# 1.net
KiCad netlist of a schematic drawn in Altium Designer
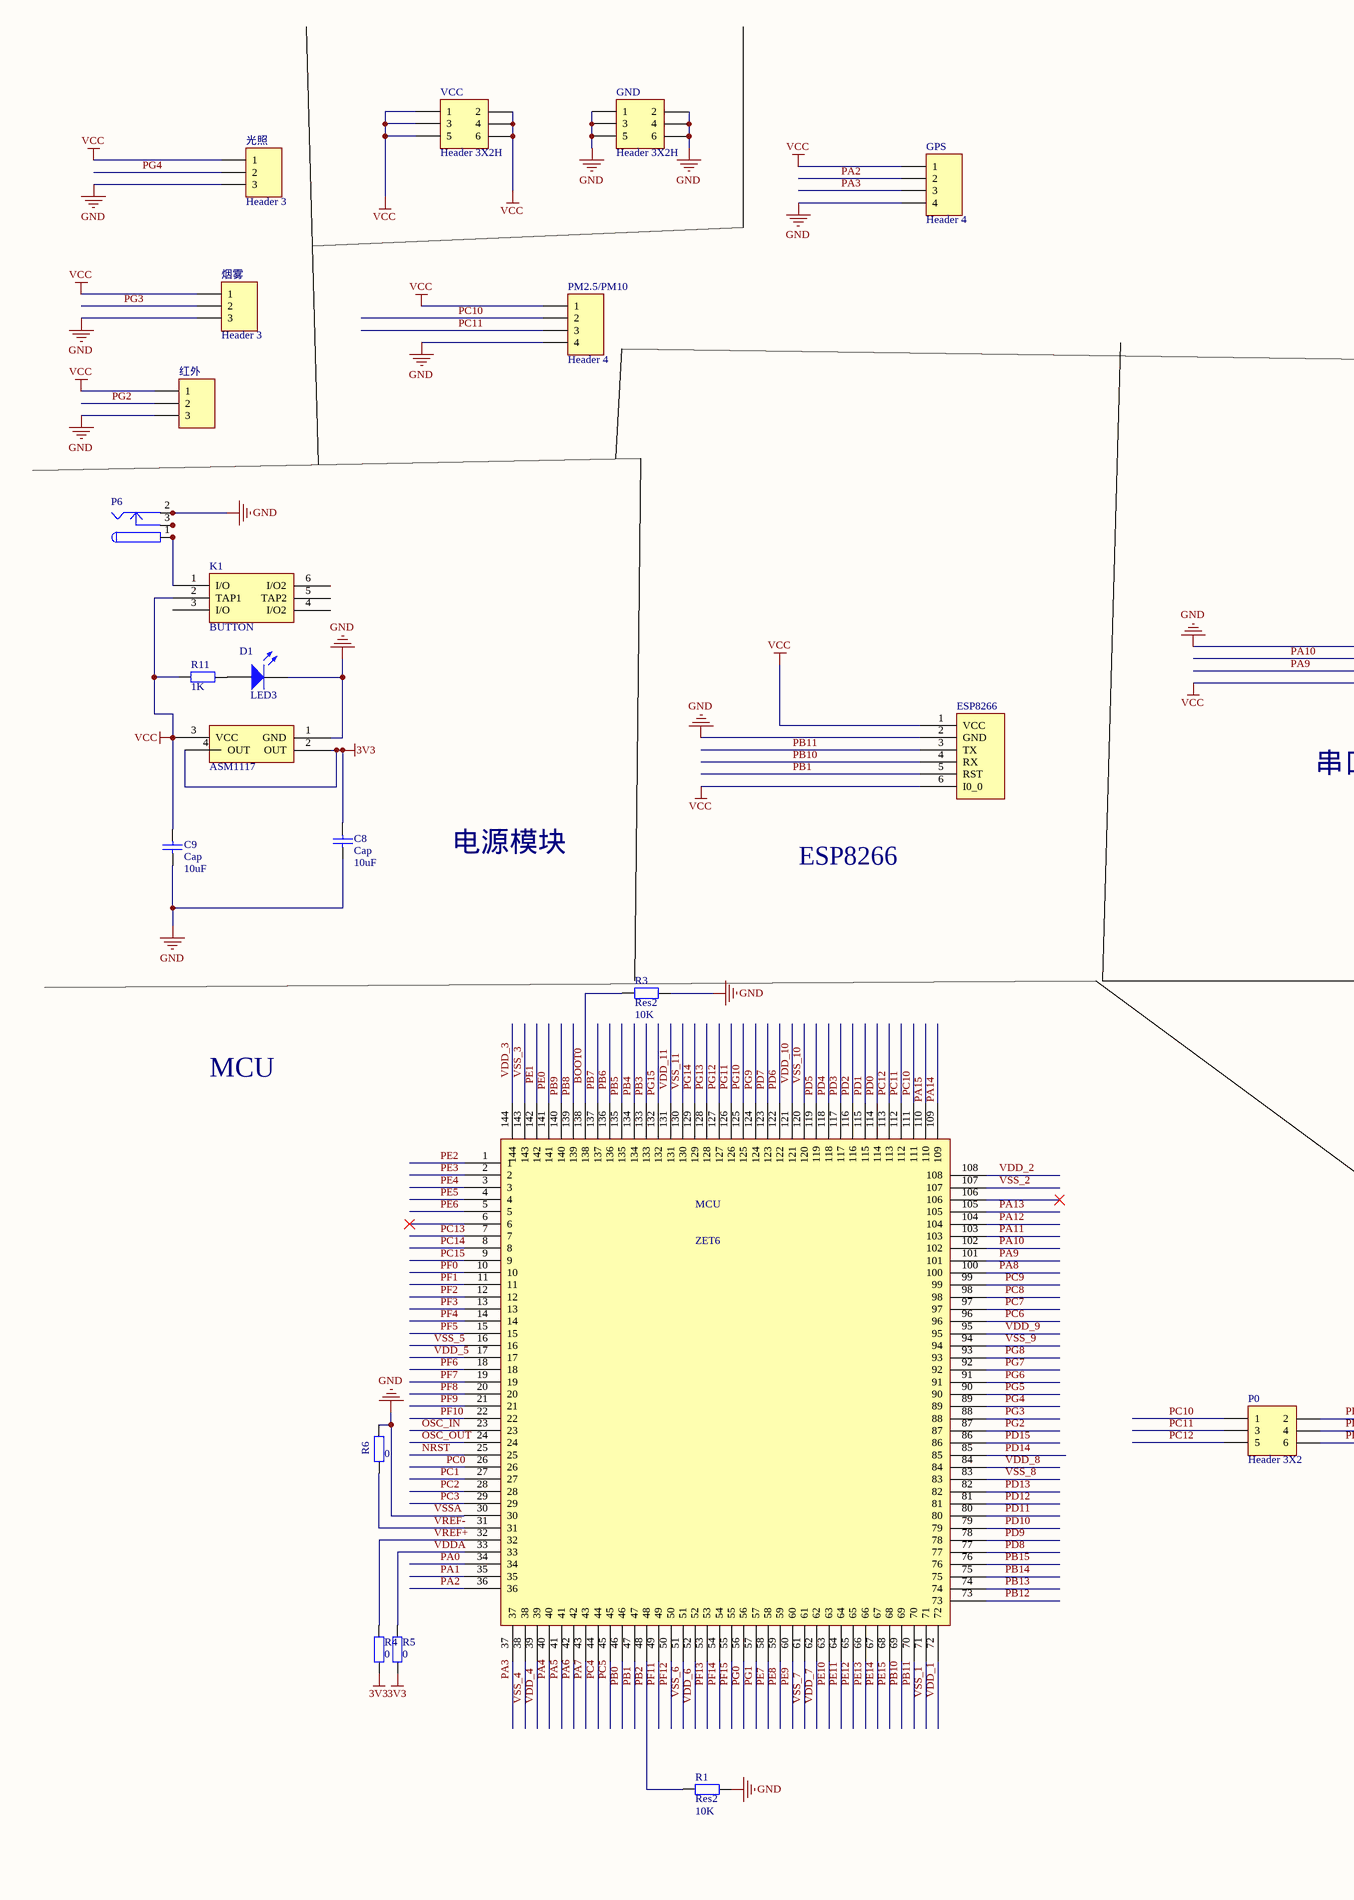
[diagram p0: 1.SchDoc, left]
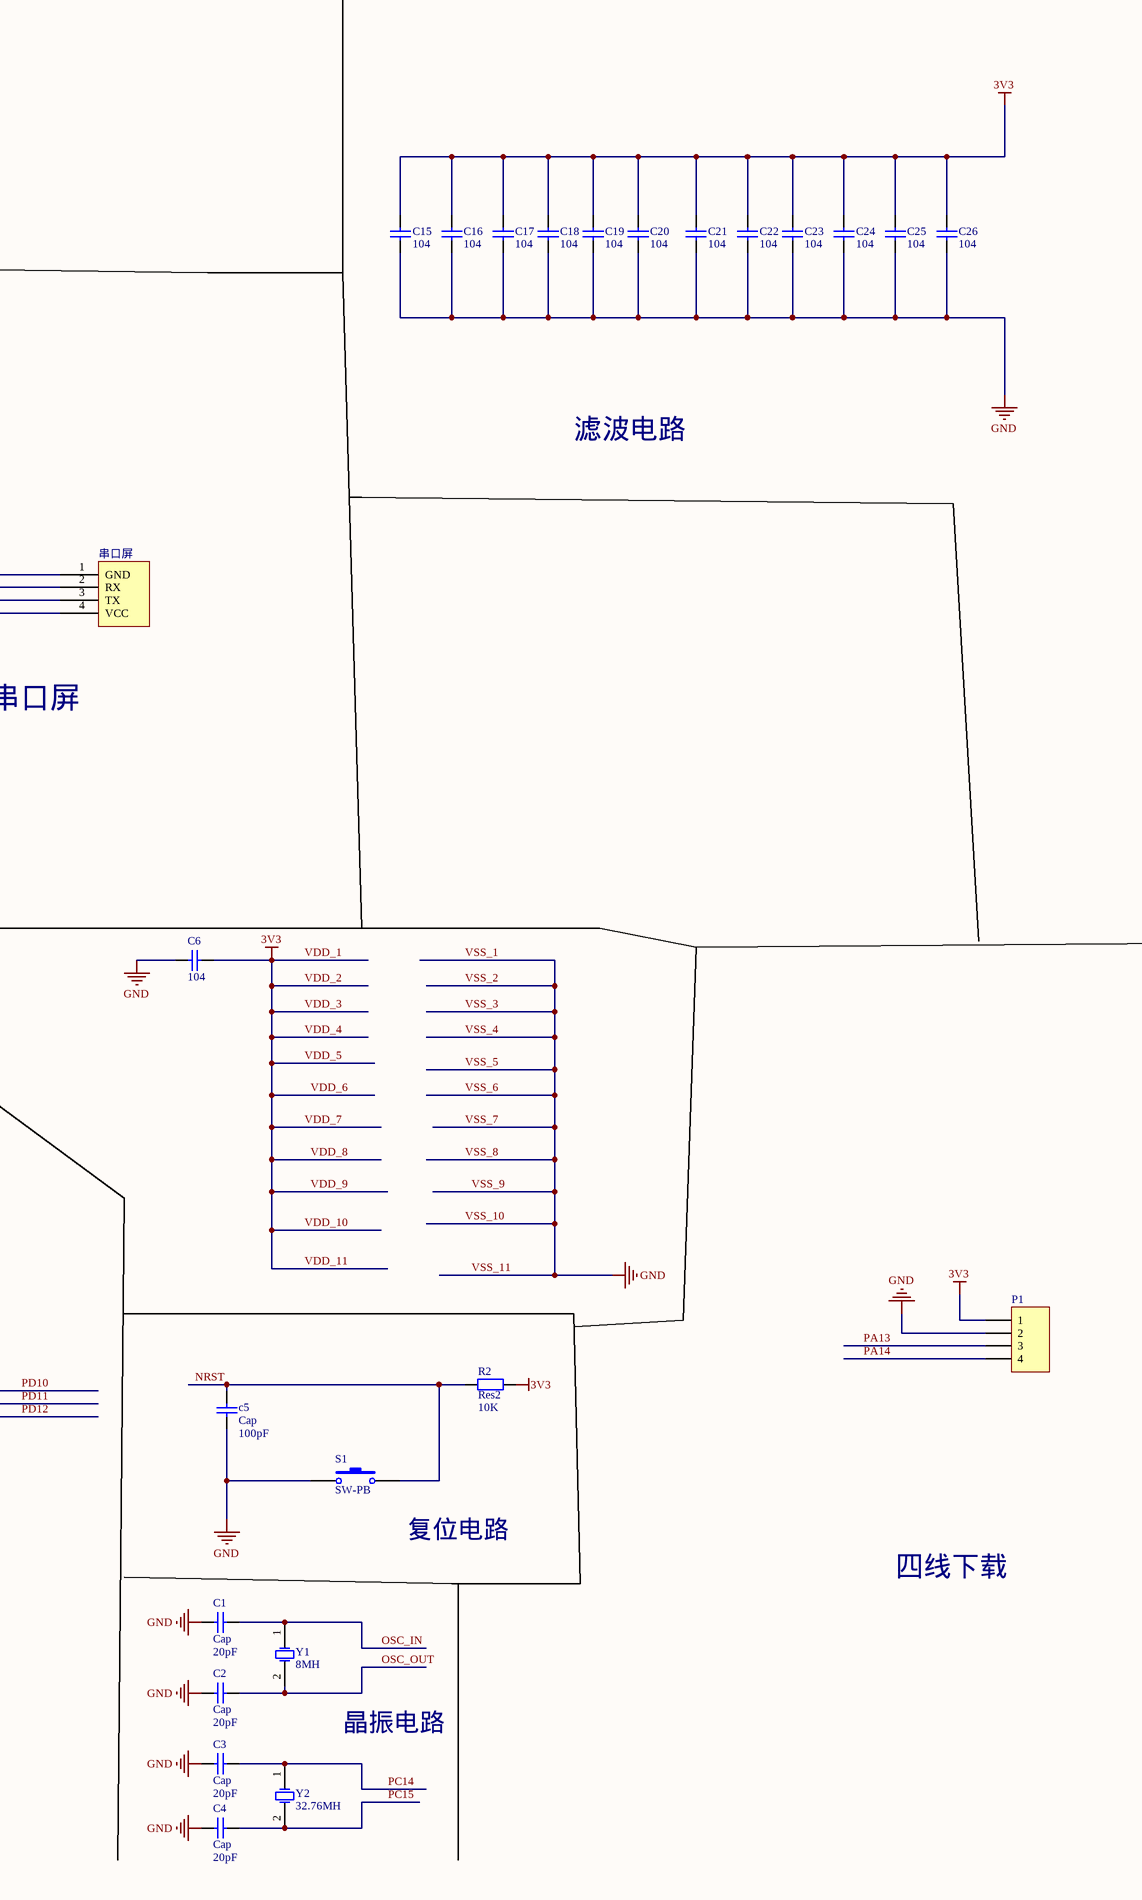
[diagram p1: 1.SchDoc, right]

(export (version "E")
  (design (tool "Eeschema 10.0.6"))
  (components
    (comp (ref "*") (value "ASM1117") (footprint "SOT-223") (libsource (lib "Schlib1") (part "ASM1117")))
    (comp (ref "C1")
      (value "Cap")
      (footprint "C0805")
      (description "Capacitor")
      (fields (field (name "ALTIUM_VALUE") "20pF") (field (name "PUBLISHER") "Altium Limited"))
      (libsource (lib "Miscellaneous Devices") (part "Cap"))
    )
    (comp (ref "C2")
      (value "Cap")
      (footprint "C0805")
      (description "Capacitor")
      (fields (field (name "ALTIUM_VALUE") "20pF") (field (name "PUBLISHER") "Altium Limited"))
      (libsource (lib "Miscellaneous Devices") (part "Cap"))
    )
    (comp (ref "C3")
      (value "Cap")
      (footprint "C0805")
      (description "Capacitor")
      (fields (field (name "ALTIUM_VALUE") "20pF") (field (name "PUBLISHER") "Altium Limited"))
      (libsource (lib "Miscellaneous Devices") (part "Cap"))
    )
    (comp (ref "C4")
      (value "Cap")
      (footprint "C0805")
      (description "Capacitor")
      (fields (field (name "ALTIUM_VALUE") "20pF") (field (name "PUBLISHER") "Altium Limited"))
      (libsource (lib "Miscellaneous Devices") (part "Cap"))
    )
    (comp (ref "c5")
      (value "Cap")
      (footprint "C0805")
      (description "Capacitor")
      (fields (field (name "ALTIUM_VALUE") "100pF") (field (name "PUBLISHER") "Altium Limited"))
      (libsource (lib "Miscellaneous Devices") (part "Cap"))
    )
    (comp (ref "C6")
      (value "104")
      (footprint "C0805")
      (description "Capacitor (Semiconductor SIM Model)")
      (fields (field (name "Comment") "Cap Semi") (field (name "PUBLISHER") "Altium Limited"))
      (libsource (lib "Miscellaneous Devices") (part "Cap Semi"))
    )
    (comp (ref "C8")
      (value "Cap")
      (footprint "C0805")
      (description "Capacitor")
      (fields (field (name "ALTIUM_VALUE") "10uF") (field (name "PUBLISHER") "Altium Limited"))
      (libsource (lib "Miscellaneous Devices") (part "Cap"))
    )
    (comp (ref "C9")
      (value "Cap")
      (footprint "C0805")
      (description "Capacitor")
      (fields (field (name "ALTIUM_VALUE") "10uF") (field (name "PUBLISHER") "Altium Limited"))
      (libsource (lib "Miscellaneous Devices") (part "Cap"))
    )
    (comp (ref "C15")
      (value "104")
      (footprint "C0805")
      (description "Capacitor")
      (fields (field (name "Comment") "Cap") (field (name "PUBLISHER") "Altium Limited"))
      (libsource (lib "Miscellaneous Devices") (part "Cap"))
    )
    (comp (ref "C16")
      (value "104")
      (footprint "C0805")
      (description "Capacitor")
      (fields (field (name "Comment") "Cap") (field (name "PUBLISHER") "Altium Limited"))
      (libsource (lib "Miscellaneous Devices") (part "Cap"))
    )
    (comp (ref "C17")
      (value "104")
      (footprint "C0805")
      (description "Capacitor")
      (fields (field (name "Comment") "Cap") (field (name "PUBLISHER") "Altium Limited"))
      (libsource (lib "Miscellaneous Devices") (part "Cap"))
    )
    (comp (ref "C18")
      (value "104")
      (footprint "C0805")
      (description "Capacitor")
      (fields (field (name "Comment") "Cap") (field (name "PUBLISHER") "Altium Limited"))
      (libsource (lib "Miscellaneous Devices") (part "Cap"))
    )
    (comp (ref "C19")
      (value "104")
      (footprint "C0805")
      (description "Capacitor")
      (fields (field (name "Comment") "Cap") (field (name "PUBLISHER") "Altium Limited"))
      (libsource (lib "Miscellaneous Devices") (part "Cap"))
    )
    (comp (ref "C20")
      (value "104")
      (footprint "C0805")
      (description "Capacitor")
      (fields (field (name "Comment") "Cap") (field (name "PUBLISHER") "Altium Limited"))
      (libsource (lib "Miscellaneous Devices") (part "Cap"))
    )
    (comp (ref "C21")
      (value "104")
      (footprint "C0805")
      (description "Capacitor")
      (fields (field (name "Comment") "Cap") (field (name "PUBLISHER") "Altium Limited"))
      (libsource (lib "Miscellaneous Devices") (part "Cap"))
    )
    (comp (ref "C22")
      (value "104")
      (footprint "C0805")
      (description "Capacitor")
      (fields (field (name "Comment") "Cap") (field (name "PUBLISHER") "Altium Limited"))
      (libsource (lib "Miscellaneous Devices") (part "Cap"))
    )
    (comp (ref "C23")
      (value "104")
      (footprint "C0805")
      (description "Capacitor")
      (fields (field (name "Comment") "Cap") (field (name "PUBLISHER") "Altium Limited"))
      (libsource (lib "Miscellaneous Devices") (part "Cap"))
    )
    (comp (ref "C24")
      (value "104")
      (footprint "C0805")
      (description "Capacitor")
      (fields (field (name "Comment") "Cap") (field (name "PUBLISHER") "Altium Limited"))
      (libsource (lib "Miscellaneous Devices") (part "Cap"))
    )
    (comp (ref "C25")
      (value "104")
      (footprint "C0805")
      (description "Capacitor")
      (fields (field (name "Comment") "Cap") (field (name "PUBLISHER") "Altium Limited"))
      (libsource (lib "Miscellaneous Devices") (part "Cap"))
    )
    (comp (ref "C26")
      (value "104")
      (footprint "C0805")
      (description "Capacitor")
      (fields (field (name "Comment") "Cap") (field (name "PUBLISHER") "Altium Limited"))
      (libsource (lib "Miscellaneous Devices") (part "Cap"))
    )
    (comp (ref "D1")
      (value "LED3")
      (footprint "RB.10")
      (description "Typical BLUE SiC LED")
      (fields (field (name "PUBLISHER") "Altium Limited"))
      (libsource (lib "Miscellaneous Devices") (part "LED3"))
    )
    (comp (ref "ESP8266") (value "A10") (footprint "HDR1X6") (libsource (lib "") (part "Component_1_1")))
    (comp (ref "GND")
      (value "Header 3X2H")
      (footprint "HDR2X3_CEN")
      (description "Header, 3-Pin, Dual row, Right Angle")
      (fields (field (name "PUBLISHER") "Altium Limited"))
      (libsource (lib "Miscellaneous Connectors") (part "Header 3X2H"))
    )
    (comp (ref "GPS")
      (value "Header 4")
      (footprint "HDR1X4")
      (description "Header, 4-Pin")
      (fields (field (name "PUBLISHER") "Altium Limited"))
      (libsource (lib "Miscellaneous Connectors") (part "Header 4"))
    )
    (comp (ref "K1") (value "BUTTON") (footprint "BTN8.5*8.5") (libsource (lib "Schlib1") (part "BUTTON")))
    (comp (ref "P0")
      (value "Header 3X2")
      (footprint "HDR2X3")
      (description "Header, 3-Pin, Dual row")
      (fields (field (name "PUBLISHER") "Altium Limited"))
      (libsource (lib "Miscellaneous Connectors") (part "Header 3X2"))
    )
    (comp (ref "P1")
      (value "Header 4")
      (footprint "HDR1X4")
      (description "Header, 4-Pin")
      (fields (field (name "PUBLISHER") "Altium Limited"))
      (libsource (lib "Miscellaneous Connectors") (part "Header 4"))
    )
    (comp (ref "P6")
      (value "PWR2.5")
      (footprint "DCIN")
      (description "Low Voltage Power Supply Connector")
      (fields (field (name "PUBLISHER") "Altium Limited"))
      (libsource (lib "Miscellaneous Connectors") (part "PWR2.5"))
    )
    (comp (ref "PM2.5/PM10")
      (value "Header 4")
      (footprint "HDR1X4")
      (description "Header, 4-Pin")
      (fields (field (name "PUBLISHER") "Altium Limited"))
      (libsource (lib "Miscellaneous Connectors") (part "Header 4"))
    )
    (comp (ref "R1")
      (value "Res2")
      (footprint "C0805")
      (description "Resistor")
      (fields (field (name "ALTIUM_VALUE") "10K") (field (name "PUBLISHER") "Altium Limited"))
      (libsource (lib "Miscellaneous Devices") (part "Res2"))
    )
    (comp (ref "R2")
      (value "Res2")
      (footprint "C0805")
      (description "Resistor")
      (fields (field (name "ALTIUM_VALUE") "10K") (field (name "PUBLISHER") "Altium Limited"))
      (libsource (lib "Miscellaneous Devices") (part "Res2"))
    )
    (comp (ref "R3")
      (value "Res2")
      (footprint "C0805")
      (description "Resistor")
      (fields (field (name "ALTIUM_VALUE") "10K") (field (name "PUBLISHER") "Altium Limited"))
      (libsource (lib "Miscellaneous Devices") (part "Res2"))
    )
    (comp (ref "R4")
      (value "0")
      (footprint "C0805")
      (description "Resistor")
      (fields (field (name "Comment") "Res2") (field (name "PUBLISHER") "Altium Limited"))
      (libsource (lib "") (part "Res2_1"))
    )
    (comp (ref "R5")
      (value "0")
      (footprint "C0805")
      (description "Resistor")
      (fields (field (name "Comment") "Res2") (field (name "PUBLISHER") "Altium Limited"))
      (libsource (lib "") (part "Res2_1"))
    )
    (comp (ref "R6")
      (value "0")
      (footprint "C0805")
      (description "Resistor")
      (fields (field (name "Comment") "Res2") (field (name "PUBLISHER") "Altium Limited"))
      (libsource (lib "") (part "Res2_1"))
    )
    (comp (ref "R11")
      (value "1K")
      (footprint "C0805")
      (description "Resistor")
      (fields (field (name "Comment") "Res2") (field (name "PUBLISHER") "Altium Limited"))
      (libsource (lib "Miscellaneous Devices") (part "Res2"))
    )
    (comp (ref "S1")
      (value "SW-PB")
      (footprint "key4")
      (description "Switch")
      (fields (field (name "PUBLISHER") "Altium Limited"))
      (libsource (lib "Miscellaneous Devices") (part "SW-PB"))
    )
    (comp (ref "VCC")
      (value "Header 3X2H")
      (footprint "HDR2X3_CEN")
      (description "Header, 3-Pin, Dual row, Right Angle")
      (fields (field (name "PUBLISHER") "Altium Limited"))
      (libsource (lib "Miscellaneous Connectors") (part "Header 3X2H"))
    )
    (comp (ref "Y1")
      (value "8MH")
      (footprint "XTAL1")
      (description "Crystal Oscillator")
      (fields (field (name "PUBLISHER") "Altium Limited"))
      (libsource (lib "Miscellaneous Devices") (part "XTAL"))
    )
    (comp (ref "Y2")
      (value "32.76MH")
      (footprint "CY-W")
      (description "Crystal Oscillator")
      (fields (field (name "PUBLISHER") "Altium Limited"))
      (libsource (lib "Miscellaneous Devices") (part "XTAL"))
    )
    (comp (ref "ZET6") (value "MCU") (footprint "LQFP144") (libsource (lib "Schlib1") (part "Component_1")))
    (comp (ref "串口屏") (value "串口屏") (footprint "HDR1X4") (libsource (lib "Schlib1") (part "串口屏")))
    (comp (ref "光照")
      (value "Header 3")
      (footprint "HDR1X3")
      (description "Header, 3-Pin")
      (fields (field (name "PUBLISHER") "Altium Limited"))
      (libsource (lib "Miscellaneous Connectors") (part "Header 3"))
    )
    (comp (ref "烟雾")
      (value "Header 3")
      (footprint "HDR1X3")
      (description "Header, 3-Pin")
      (fields (field (name "PUBLISHER") "Altium Limited"))
      (libsource (lib "Miscellaneous Connectors") (part "Header 3"))
    )
    (comp (ref "红外")
      (value "Header 3")
      (footprint "HDR1X3")
      (description "Header, 3-Pin")
      (fields (field (name "PUBLISHER") "Altium Limited"))
      (libsource (lib "Miscellaneous Connectors") (part "Header 3"))
    )
  )
  (nets
    (net (code "1") (name "/BOOT0") (class "Default")
      (node (ref "R3") (pin "1") (pinfunction "1_1") (pintype "passive"))
      (node (ref "ZET6") (pin "138") (pinfunction "138_138") (pintype "passive"))
    )
    (net (code "2") (name "/NRST") (class "Default")
      (node (ref "R2") (pin "1") (pinfunction "1_1") (pintype "passive"))
      (node (ref "S1") (pin "2") (pinfunction "2_2") (pintype "passive"))
      (node (ref "ZET6") (pin "25") (pinfunction "25_25") (pintype "passive"))
      (node (ref "c5") (pin "2") (pinfunction "2_2") (pintype "passive"))
    )
    (net (code "3") (name "/OSC_IN") (class "Default")
      (node (ref "C1") (pin "2") (pinfunction "2_2") (pintype "passive"))
      (node (ref "Y1") (pin "1") (pinfunction "OSC1_1") (pintype "passive"))
      (node (ref "ZET6") (pin "23") (pinfunction "23_23") (pintype "passive"))
    )
    (net (code "4") (name "/OSC_OUT") (class "Default")
      (node (ref "C2") (pin "2") (pinfunction "2_2") (pintype "passive"))
      (node (ref "Y1") (pin "2") (pinfunction "OSC2_2") (pintype "passive"))
      (node (ref "ZET6") (pin "24") (pinfunction "24_24") (pintype "passive"))
    )
    (net (code "5") (name "/PA0") (class "Default")
      (node (ref "ZET6") (pin "34") (pinfunction "34_34") (pintype "passive"))
    )
    (net (code "6") (name "/PA1") (class "Default")
      (node (ref "ZET6") (pin "35") (pinfunction "35_35") (pintype "passive"))
    )
    (net (code "7") (name "/PA2") (class "Default")
      (node (ref "GPS") (pin "2") (pinfunction "2_2") (pintype "passive"))
      (node (ref "ZET6") (pin "36") (pinfunction "36_36") (pintype "passive"))
    )
    (net (code "8") (name "/PA3") (class "Default")
      (node (ref "GPS") (pin "3") (pinfunction "3_3") (pintype "passive"))
      (node (ref "ZET6") (pin "37") (pinfunction "37_37") (pintype "passive"))
    )
    (net (code "9") (name "/PA4") (class "Default")
      (node (ref "ZET6") (pin "40") (pinfunction "40_40") (pintype "passive"))
    )
    (net (code "10") (name "/PA5") (class "Default")
      (node (ref "ZET6") (pin "41") (pinfunction "41_41") (pintype "passive"))
    )
    (net (code "11") (name "/PA6") (class "Default")
      (node (ref "ZET6") (pin "42") (pinfunction "42_42") (pintype "passive"))
    )
    (net (code "12") (name "/PA7") (class "Default")
      (node (ref "ZET6") (pin "43") (pinfunction "43_43") (pintype "passive"))
    )
    (net (code "13") (name "/PA8") (class "Default")
      (node (ref "ZET6") (pin "100") (pinfunction "100_100") (pintype "passive"))
    )
    (net (code "14") (name "/PA9") (class "Default")
      (node (ref "ZET6") (pin "101") (pinfunction "101_101") (pintype "passive"))
      (node (ref "串口屏") (pin "3") (pinfunction "TX_3") (pintype "passive"))
    )
    (net (code "15") (name "/PA10") (class "Default")
      (node (ref "ZET6") (pin "102") (pinfunction "102_102") (pintype "passive"))
      (node (ref "串口屏") (pin "2") (pinfunction "RX_2") (pintype "passive"))
    )
    (net (code "16") (name "/PA11") (class "Default")
      (node (ref "ZET6") (pin "103") (pinfunction "103_103") (pintype "passive"))
    )
    (net (code "17") (name "/PA12") (class "Default")
      (node (ref "ZET6") (pin "104") (pinfunction "104_104") (pintype "passive"))
    )
    (net (code "18") (name "/PA13") (class "Default")
      (node (ref "P1") (pin "3") (pinfunction "3_3") (pintype "passive"))
      (node (ref "ZET6") (pin "105") (pinfunction "105_105") (pintype "passive"))
    )
    (net (code "19") (name "/PA14") (class "Default")
      (node (ref "P1") (pin "4") (pinfunction "4_4") (pintype "passive"))
      (node (ref "ZET6") (pin "109") (pinfunction "109_109") (pintype "passive"))
    )
    (net (code "20") (name "/PA15") (class "Default")
      (node (ref "ZET6") (pin "110") (pinfunction "110_110") (pintype "passive"))
    )
    (net (code "21") (name "/PB0") (class "Default")
      (node (ref "ZET6") (pin "46") (pinfunction "46_46") (pintype "passive"))
    )
    (net (code "22") (name "/PB1") (class "Default")
      (node (ref "ESP8266") (pin "5") (pinfunction "RST_5") (pintype "passive"))
      (node (ref "ZET6") (pin "47") (pinfunction "47_47") (pintype "passive"))
    )
    (net (code "23") (name "/PB2") (class "Default")
      (node (ref "R1") (pin "1") (pinfunction "1_1") (pintype "passive"))
      (node (ref "ZET6") (pin "48") (pinfunction "48_48") (pintype "passive"))
    )
    (net (code "24") (name "/PB3") (class "Default")
      (node (ref "ZET6") (pin "133") (pinfunction "133_133") (pintype "passive"))
    )
    (net (code "25") (name "/PB4") (class "Default")
      (node (ref "ZET6") (pin "134") (pinfunction "134_134") (pintype "passive"))
    )
    (net (code "26") (name "/PB5") (class "Default")
      (node (ref "ZET6") (pin "135") (pinfunction "135_135") (pintype "passive"))
    )
    (net (code "27") (name "/PB6") (class "Default")
      (node (ref "ZET6") (pin "136") (pinfunction "136_136") (pintype "passive"))
    )
    (net (code "28") (name "/PB7") (class "Default")
      (node (ref "ZET6") (pin "137") (pinfunction "137_137") (pintype "passive"))
    )
    (net (code "29") (name "/PB8") (class "Default")
      (node (ref "ZET6") (pin "139") (pinfunction "139_139") (pintype "passive"))
    )
    (net (code "30") (name "/PB9") (class "Default")
      (node (ref "ZET6") (pin "140") (pinfunction "140_140") (pintype "passive"))
    )
    (net (code "31") (name "/PB10") (class "Default")
      (node (ref "ESP8266") (pin "4") (pinfunction "RX_4") (pintype "passive"))
      (node (ref "ZET6") (pin "69") (pinfunction "69_69") (pintype "passive"))
    )
    (net (code "32") (name "/PB11") (class "Default")
      (node (ref "ESP8266") (pin "3") (pinfunction "TX_3") (pintype "passive"))
      (node (ref "ZET6") (pin "70") (pinfunction "70_70") (pintype "passive"))
    )
    (net (code "33") (name "/PB12") (class "Default")
      (node (ref "ZET6") (pin "73") (pinfunction "73_73") (pintype "passive"))
    )
    (net (code "34") (name "/PB13") (class "Default")
      (node (ref "ZET6") (pin "74") (pinfunction "74_74") (pintype "passive"))
    )
    (net (code "35") (name "/PB14") (class "Default")
      (node (ref "ZET6") (pin "75") (pinfunction "75_75") (pintype "passive"))
    )
    (net (code "36") (name "/PB15") (class "Default")
      (node (ref "ZET6") (pin "76") (pinfunction "76_76") (pintype "passive"))
    )
    (net (code "37") (name "/PC0") (class "Default")
      (node (ref "ZET6") (pin "26") (pinfunction "26_26") (pintype "passive"))
    )
    (net (code "38") (name "/PC1") (class "Default")
      (node (ref "ZET6") (pin "27") (pinfunction "27_27") (pintype "passive"))
    )
    (net (code "39") (name "/PC2") (class "Default")
      (node (ref "ZET6") (pin "28") (pinfunction "28_28") (pintype "passive"))
    )
    (net (code "40") (name "/PC3") (class "Default")
      (node (ref "ZET6") (pin "29") (pinfunction "29_29") (pintype "passive"))
    )
    (net (code "41") (name "/PC4") (class "Default")
      (node (ref "ZET6") (pin "44") (pinfunction "44_44") (pintype "passive"))
    )
    (net (code "42") (name "/PC5") (class "Default")
      (node (ref "ZET6") (pin "45") (pinfunction "45_45") (pintype "passive"))
    )
    (net (code "43") (name "/PC6") (class "Default")
      (node (ref "ZET6") (pin "96") (pinfunction "96_96") (pintype "passive"))
    )
    (net (code "44") (name "/PC7") (class "Default")
      (node (ref "ZET6") (pin "97") (pinfunction "97_97") (pintype "passive"))
    )
    (net (code "45") (name "/PC8") (class "Default")
      (node (ref "ZET6") (pin "98") (pinfunction "98_98") (pintype "passive"))
    )
    (net (code "46") (name "/PC9") (class "Default")
      (node (ref "ZET6") (pin "99") (pinfunction "99_99") (pintype "passive"))
    )
    (net (code "47") (name "/PC10") (class "Default")
      (node (ref "P0") (pin "1") (pinfunction "1_1") (pintype "passive"))
      (node (ref "PM2.5/PM10") (pin "2") (pinfunction "2_2") (pintype "passive"))
      (node (ref "ZET6") (pin "111") (pinfunction "111_111") (pintype "passive"))
    )
    (net (code "48") (name "/PC11") (class "Default")
      (node (ref "P0") (pin "3") (pinfunction "3_3") (pintype "passive"))
      (node (ref "PM2.5/PM10") (pin "3") (pinfunction "3_3") (pintype "passive"))
      (node (ref "ZET6") (pin "112") (pinfunction "112_112") (pintype "passive"))
    )
    (net (code "49") (name "/PC12") (class "Default")
      (node (ref "P0") (pin "5") (pinfunction "5_5") (pintype "passive"))
      (node (ref "ZET6") (pin "113") (pinfunction "113_113") (pintype "passive"))
    )
    (net (code "50") (name "/PC13") (class "Default")
      (node (ref "ZET6") (pin "7") (pinfunction "7_7") (pintype "passive"))
    )
    (net (code "51") (name "/PC14") (class "Default")
      (node (ref "C3") (pin "2") (pinfunction "2_2") (pintype "passive"))
      (node (ref "Y2") (pin "1") (pinfunction "OSC1_1") (pintype "passive"))
      (node (ref "ZET6") (pin "8") (pinfunction "8_8") (pintype "passive"))
    )
    (net (code "52") (name "/PC15") (class "Default")
      (node (ref "C4") (pin "2") (pinfunction "2_2") (pintype "passive"))
      (node (ref "Y2") (pin "2") (pinfunction "OSC2_2") (pintype "passive"))
      (node (ref "ZET6") (pin "9") (pinfunction "9_9") (pintype "passive"))
    )
    (net (code "53") (name "/PD0") (class "Default")
      (node (ref "ZET6") (pin "114") (pinfunction "114_114") (pintype "passive"))
    )
    (net (code "54") (name "/PD1") (class "Default")
      (node (ref "ZET6") (pin "115") (pinfunction "115_115") (pintype "passive"))
    )
    (net (code "55") (name "/PD2") (class "Default")
      (node (ref "ZET6") (pin "116") (pinfunction "116_116") (pintype "passive"))
    )
    (net (code "56") (name "/PD3") (class "Default")
      (node (ref "ZET6") (pin "117") (pinfunction "117_117") (pintype "passive"))
    )
    (net (code "57") (name "/PD4") (class "Default")
      (node (ref "ZET6") (pin "118") (pinfunction "118_118") (pintype "passive"))
    )
    (net (code "58") (name "/PD5") (class "Default")
      (node (ref "ZET6") (pin "119") (pinfunction "119_119") (pintype "passive"))
    )
    (net (code "59") (name "/PD6") (class "Default")
      (node (ref "ZET6") (pin "122") (pinfunction "122_122") (pintype "passive"))
    )
    (net (code "60") (name "/PD7") (class "Default")
      (node (ref "ZET6") (pin "123") (pinfunction "123_123") (pintype "passive"))
    )
    (net (code "61") (name "/PD8") (class "Default")
      (node (ref "ZET6") (pin "77") (pinfunction "77_77") (pintype "passive"))
    )
    (net (code "62") (name "/PD9") (class "Default")
      (node (ref "ZET6") (pin "78") (pinfunction "78_78") (pintype "passive"))
    )
    (net (code "63") (name "/PD10") (class "Default")
      (node (ref "P0") (pin "2") (pinfunction "2_2") (pintype "passive"))
      (node (ref "ZET6") (pin "79") (pinfunction "79_79") (pintype "passive"))
    )
    (net (code "64") (name "/PD11") (class "Default")
      (node (ref "P0") (pin "4") (pinfunction "4_4") (pintype "passive"))
      (node (ref "ZET6") (pin "80") (pinfunction "80_80") (pintype "passive"))
    )
    (net (code "65") (name "/PD12") (class "Default")
      (node (ref "P0") (pin "6") (pinfunction "6_6") (pintype "passive"))
      (node (ref "ZET6") (pin "81") (pinfunction "81_81") (pintype "passive"))
    )
    (net (code "66") (name "/PD13") (class "Default")
      (node (ref "ZET6") (pin "82") (pinfunction "82_82") (pintype "passive"))
    )
    (net (code "67") (name "/PD14") (class "Default")
      (node (ref "ZET6") (pin "85") (pinfunction "85_85") (pintype "passive"))
    )
    (net (code "68") (name "/PD15") (class "Default")
      (node (ref "ZET6") (pin "86") (pinfunction "86_86") (pintype "passive"))
    )
    (net (code "69") (name "/PE0") (class "Default")
      (node (ref "ZET6") (pin "141") (pinfunction "141_141") (pintype "passive"))
    )
    (net (code "70") (name "/PE1") (class "Default")
      (node (ref "ZET6") (pin "142") (pinfunction "142_142") (pintype "passive"))
    )
    (net (code "71") (name "/PE2") (class "Default")
      (node (ref "ZET6") (pin "1") (pinfunction "1_1") (pintype "passive"))
    )
    (net (code "72") (name "/PE3") (class "Default")
      (node (ref "ZET6") (pin "2") (pinfunction "2_2") (pintype "passive"))
    )
    (net (code "73") (name "/PE4") (class "Default")
      (node (ref "ZET6") (pin "3") (pinfunction "3_3") (pintype "passive"))
    )
    (net (code "74") (name "/PE5") (class "Default")
      (node (ref "ZET6") (pin "4") (pinfunction "4_4") (pintype "passive"))
    )
    (net (code "75") (name "/PE6") (class "Default")
      (node (ref "ZET6") (pin "5") (pinfunction "5_5") (pintype "passive"))
    )
    (net (code "76") (name "/PE7") (class "Default")
      (node (ref "ZET6") (pin "58") (pinfunction "58_58") (pintype "passive"))
    )
    (net (code "77") (name "/PE8") (class "Default")
      (node (ref "ZET6") (pin "59") (pinfunction "59_59") (pintype "passive"))
    )
    (net (code "78") (name "/PE9") (class "Default")
      (node (ref "ZET6") (pin "60") (pinfunction "60_60") (pintype "passive"))
    )
    (net (code "79") (name "/PE10") (class "Default")
      (node (ref "ZET6") (pin "63") (pinfunction "63_63") (pintype "passive"))
    )
    (net (code "80") (name "/PE11") (class "Default")
      (node (ref "ZET6") (pin "64") (pinfunction "64_64") (pintype "passive"))
    )
    (net (code "81") (name "/PE12") (class "Default")
      (node (ref "ZET6") (pin "65") (pinfunction "65_65") (pintype "passive"))
    )
    (net (code "82") (name "/PE13") (class "Default")
      (node (ref "ZET6") (pin "66") (pinfunction "66_66") (pintype "passive"))
    )
    (net (code "83") (name "/PE14") (class "Default")
      (node (ref "ZET6") (pin "67") (pinfunction "67_67") (pintype "passive"))
    )
    (net (code "84") (name "/PE15") (class "Default")
      (node (ref "ZET6") (pin "68") (pinfunction "68_68") (pintype "passive"))
    )
    (net (code "85") (name "/PF0") (class "Default")
      (node (ref "ZET6") (pin "10") (pinfunction "10_10") (pintype "passive"))
    )
    (net (code "86") (name "/PF1") (class "Default")
      (node (ref "ZET6") (pin "11") (pinfunction "11_11") (pintype "passive"))
    )
    (net (code "87") (name "/PF2") (class "Default")
      (node (ref "ZET6") (pin "12") (pinfunction "12_12") (pintype "passive"))
    )
    (net (code "88") (name "/PF3") (class "Default")
      (node (ref "ZET6") (pin "13") (pinfunction "13_13") (pintype "passive"))
    )
    (net (code "89") (name "/PF4") (class "Default")
      (node (ref "ZET6") (pin "14") (pinfunction "14_14") (pintype "passive"))
    )
    (net (code "90") (name "/PF5") (class "Default")
      (node (ref "ZET6") (pin "15") (pinfunction "15_15") (pintype "passive"))
    )
    (net (code "91") (name "/PF6") (class "Default")
      (node (ref "ZET6") (pin "18") (pinfunction "18_18") (pintype "passive"))
    )
    (net (code "92") (name "/PF7") (class "Default")
      (node (ref "ZET6") (pin "19") (pinfunction "19_19") (pintype "passive"))
    )
    (net (code "93") (name "/PF8") (class "Default")
      (node (ref "ZET6") (pin "20") (pinfunction "20_20") (pintype "passive"))
    )
    (net (code "94") (name "/PF9") (class "Default")
      (node (ref "ZET6") (pin "21") (pinfunction "21_21") (pintype "passive"))
    )
    (net (code "95") (name "/PF10") (class "Default")
      (node (ref "ZET6") (pin "22") (pinfunction "22_22") (pintype "passive"))
    )
    (net (code "96") (name "/PF11") (class "Default")
      (node (ref "ZET6") (pin "49") (pinfunction "49_49") (pintype "passive"))
    )
    (net (code "97") (name "/PF12") (class "Default")
      (node (ref "ZET6") (pin "50") (pinfunction "50_50") (pintype "passive"))
    )
    (net (code "98") (name "/PF13") (class "Default")
      (node (ref "ZET6") (pin "53") (pinfunction "53_53") (pintype "passive"))
    )
    (net (code "99") (name "/PF14") (class "Default")
      (node (ref "ZET6") (pin "54") (pinfunction "54_54") (pintype "passive"))
    )
    (net (code "100") (name "/PF15") (class "Default")
      (node (ref "ZET6") (pin "55") (pinfunction "55_55") (pintype "passive"))
    )
    (net (code "101") (name "/PG0") (class "Default")
      (node (ref "ZET6") (pin "56") (pinfunction "56_56") (pintype "passive"))
    )
    (net (code "102") (name "/PG1") (class "Default")
      (node (ref "ZET6") (pin "57") (pinfunction "57_57") (pintype "passive"))
    )
    (net (code "103") (name "/PG2") (class "Default")
      (node (ref "ZET6") (pin "87") (pinfunction "87_87") (pintype "passive"))
      (node (ref "红外") (pin "2") (pinfunction "2_2") (pintype "passive"))
    )
    (net (code "104") (name "/PG3") (class "Default")
      (node (ref "ZET6") (pin "88") (pinfunction "88_88") (pintype "passive"))
      (node (ref "烟雾") (pin "2") (pinfunction "2_2") (pintype "passive"))
    )
    (net (code "105") (name "/PG4") (class "Default")
      (node (ref "ZET6") (pin "89") (pinfunction "89_89") (pintype "passive"))
      (node (ref "光照") (pin "2") (pinfunction "2_2") (pintype "passive"))
    )
    (net (code "106") (name "/PG5") (class "Default")
      (node (ref "ZET6") (pin "90") (pinfunction "90_90") (pintype "passive"))
    )
    (net (code "107") (name "/PG6") (class "Default")
      (node (ref "ZET6") (pin "91") (pinfunction "91_91") (pintype "passive"))
    )
    (net (code "108") (name "/PG7") (class "Default")
      (node (ref "ZET6") (pin "92") (pinfunction "92_92") (pintype "passive"))
    )
    (net (code "109") (name "/PG8") (class "Default")
      (node (ref "ZET6") (pin "93") (pinfunction "93_93") (pintype "passive"))
    )
    (net (code "110") (name "/PG9") (class "Default")
      (node (ref "ZET6") (pin "124") (pinfunction "124_124") (pintype "passive"))
    )
    (net (code "111") (name "/PG10") (class "Default")
      (node (ref "ZET6") (pin "125") (pinfunction "125_125") (pintype "passive"))
    )
    (net (code "112") (name "/PG11") (class "Default")
      (node (ref "ZET6") (pin "126") (pinfunction "126_126") (pintype "passive"))
    )
    (net (code "113") (name "/PG12") (class "Default")
      (node (ref "ZET6") (pin "127") (pinfunction "127_127") (pintype "passive"))
    )
    (net (code "114") (name "/PG13") (class "Default")
      (node (ref "ZET6") (pin "128") (pinfunction "128_128") (pintype "passive"))
    )
    (net (code "115") (name "/PG14") (class "Default")
      (node (ref "ZET6") (pin "129") (pinfunction "129_129") (pintype "passive"))
    )
    (net (code "116") (name "/PG15") (class "Default")
      (node (ref "ZET6") (pin "132") (pinfunction "132_132") (pintype "passive"))
    )
    (net (code "117") (name "/VDDA") (class "Default")
      (node (ref "R5") (pin "2") (pinfunction "2_2") (pintype "passive"))
      (node (ref "ZET6") (pin "33") (pinfunction "33_33") (pintype "passive"))
    )
    (net (code "118") (name "/VREF+") (class "Default")
      (node (ref "R4") (pin "2") (pinfunction "2_2") (pintype "passive"))
      (node (ref "ZET6") (pin "32") (pinfunction "32_32") (pintype "passive"))
    )
    (net (code "119") (name "/VREF-") (class "Default")
      (node (ref "R6") (pin "1") (pinfunction "1_1") (pintype "passive"))
      (node (ref "ZET6") (pin "31") (pinfunction "31_31") (pintype "passive"))
    )
    (net (code "120") (name "3V3") (class "Default")
      (node (ref "*") (pin "2") (pinfunction "OUT_2") (pintype "passive"))
      (node (ref "*") (pin "4") (pinfunction "OUT_4") (pintype "passive"))
      (node (ref "C15") (pin "2") (pinfunction "2_2") (pintype "passive"))
      (node (ref "C16") (pin "2") (pinfunction "2_2") (pintype "passive"))
      (node (ref "C17") (pin "1") (pinfunction "1_1") (pintype "passive"))
      (node (ref "C18") (pin "2") (pinfunction "2_2") (pintype "passive"))
      (node (ref "C19") (pin "2") (pinfunction "2_2") (pintype "passive"))
      (node (ref "C20") (pin "2") (pinfunction "2_2") (pintype "passive"))
      (node (ref "C21") (pin "2") (pinfunction "2_2") (pintype "passive"))
      (node (ref "C22") (pin "2") (pinfunction "2_2") (pintype "passive"))
      (node (ref "C23") (pin "2") (pinfunction "2_2") (pintype "passive"))
      (node (ref "C24") (pin "2") (pinfunction "2_2") (pintype "passive"))
      (node (ref "C25") (pin "2") (pinfunction "2_2") (pintype "passive"))
      (node (ref "C26") (pin "2") (pinfunction "2_2") (pintype "passive"))
      (node (ref "C6") (pin "2") (pinfunction "2_2") (pintype "passive"))
      (node (ref "C8") (pin "2") (pinfunction "2_2") (pintype "passive"))
      (node (ref "P1") (pin "1") (pinfunction "1_1") (pintype "passive"))
      (node (ref "R2") (pin "2") (pinfunction "2_2") (pintype "passive"))
      (node (ref "R4") (pin "1") (pinfunction "1_1") (pintype "passive"))
      (node (ref "R5") (pin "1") (pinfunction "1_1") (pintype "passive"))
      (node (ref "ZET6") (pin "108") (pinfunction "108_108") (pintype "passive"))
      (node (ref "ZET6") (pin "121") (pinfunction "121_121") (pintype "passive"))
      (node (ref "ZET6") (pin "131") (pinfunction "131_131") (pintype "passive"))
      (node (ref "ZET6") (pin "144") (pinfunction "144_144") (pintype "passive"))
      (node (ref "ZET6") (pin "17") (pinfunction "17_17") (pintype "passive"))
      (node (ref "ZET6") (pin "39") (pinfunction "39_39") (pintype "passive"))
      (node (ref "ZET6") (pin "52") (pinfunction "52_52") (pintype "passive"))
      (node (ref "ZET6") (pin "62") (pinfunction "62_62") (pintype "passive"))
      (node (ref "ZET6") (pin "72") (pinfunction "72_72") (pintype "passive"))
      (node (ref "ZET6") (pin "84") (pinfunction "84_84") (pintype "passive"))
      (node (ref "ZET6") (pin "95") (pinfunction "95_95") (pintype "passive"))
    )
    (net (code "121") (name "GND") (class "Default")
      (node (ref "*") (pin "1") (pinfunction "GND_1") (pintype "passive"))
      (node (ref "C1") (pin "1") (pinfunction "1_1") (pintype "passive"))
      (node (ref "C15") (pin "1") (pinfunction "1_1") (pintype "passive"))
      (node (ref "C16") (pin "1") (pinfunction "1_1") (pintype "passive"))
      (node (ref "C17") (pin "2") (pinfunction "2_2") (pintype "passive"))
      (node (ref "C18") (pin "1") (pinfunction "1_1") (pintype "passive"))
      (node (ref "C19") (pin "1") (pinfunction "1_1") (pintype "passive"))
      (node (ref "C2") (pin "1") (pinfunction "1_1") (pintype "passive"))
      (node (ref "C20") (pin "1") (pinfunction "1_1") (pintype "passive"))
      (node (ref "C21") (pin "1") (pinfunction "1_1") (pintype "passive"))
      (node (ref "C22") (pin "1") (pinfunction "1_1") (pintype "passive"))
      (node (ref "C23") (pin "1") (pinfunction "1_1") (pintype "passive"))
      (node (ref "C24") (pin "1") (pinfunction "1_1") (pintype "passive"))
      (node (ref "C25") (pin "1") (pinfunction "1_1") (pintype "passive"))
      (node (ref "C26") (pin "1") (pinfunction "1_1") (pintype "passive"))
      (node (ref "C3") (pin "1") (pinfunction "1_1") (pintype "passive"))
      (node (ref "C4") (pin "1") (pinfunction "1_1") (pintype "passive"))
      (node (ref "C6") (pin "1") (pinfunction "1_1") (pintype "passive"))
      (node (ref "C8") (pin "1") (pinfunction "1_1") (pintype "passive"))
      (node (ref "C9") (pin "1") (pinfunction "1_1") (pintype "passive"))
      (node (ref "D1") (pin "2") (pinfunction "K_2") (pintype "passive"))
      (node (ref "ESP8266") (pin "2") (pinfunction "GND_2") (pintype "passive"))
      (node (ref "GND") (pin "1") (pinfunction "1_1") (pintype "passive"))
      (node (ref "GND") (pin "2") (pinfunction "2_2") (pintype "passive"))
      (node (ref "GND") (pin "3") (pinfunction "3_3") (pintype "passive"))
      (node (ref "GND") (pin "4") (pinfunction "4_4") (pintype "passive"))
      (node (ref "GND") (pin "5") (pinfunction "5_5") (pintype "passive"))
      (node (ref "GND") (pin "6") (pinfunction "6_6") (pintype "passive"))
      (node (ref "GPS") (pin "4") (pinfunction "4_4") (pintype "passive"))
      (node (ref "P1") (pin "2") (pinfunction "2_2") (pintype "passive"))
      (node (ref "P6") (pin "2") (pinfunction "2_2") (pintype "power_in"))
      (node (ref "P6") (pin "2A") (pinfunction "2A_2A") (pintype "power_in"))
      (node (ref "P6") (pin "2B") (pinfunction "2B_2B") (pintype "power_in"))
      (node (ref "PM2.5/PM10") (pin "4") (pinfunction "4_4") (pintype "passive"))
      (node (ref "R1") (pin "2") (pinfunction "2_2") (pintype "passive"))
      (node (ref "R3") (pin "2") (pinfunction "2_2") (pintype "passive"))
      (node (ref "R6") (pin "2") (pinfunction "2_2") (pintype "passive"))
      (node (ref "S1") (pin "1") (pinfunction "1_1") (pintype "passive"))
      (node (ref "ZET6") (pin "107") (pinfunction "107_107") (pintype "passive"))
      (node (ref "ZET6") (pin "120") (pinfunction "120_120") (pintype "passive"))
      (node (ref "ZET6") (pin "130") (pinfunction "130_130") (pintype "passive"))
      (node (ref "ZET6") (pin "143") (pinfunction "143_143") (pintype "passive"))
      (node (ref "ZET6") (pin "16") (pinfunction "16_16") (pintype "passive"))
      (node (ref "ZET6") (pin "30") (pinfunction "30_30") (pintype "passive"))
      (node (ref "ZET6") (pin "38") (pinfunction "38_38") (pintype "passive"))
      (node (ref "ZET6") (pin "51") (pinfunction "51_51") (pintype "passive"))
      (node (ref "ZET6") (pin "61") (pinfunction "61_61") (pintype "passive"))
      (node (ref "ZET6") (pin "71") (pinfunction "71_71") (pintype "passive"))
      (node (ref "ZET6") (pin "83") (pinfunction "83_83") (pintype "passive"))
      (node (ref "ZET6") (pin "94") (pinfunction "94_94") (pintype "passive"))
      (node (ref "c5") (pin "1") (pinfunction "1_1") (pintype "passive"))
      (node (ref "串口屏") (pin "1") (pinfunction "GND_1") (pintype "passive"))
      (node (ref "光照") (pin "3") (pinfunction "3_3") (pintype "passive"))
      (node (ref "烟雾") (pin "3") (pinfunction "3_3") (pintype "passive"))
      (node (ref "红外") (pin "3") (pinfunction "3_3") (pintype "passive"))
    )
    (net (code "122") (name "Net-(D1-A)") (class "Default")
      (node (ref "D1") (pin "1") (pinfunction "A_1") (pintype "passive"))
      (node (ref "R11") (pin "2") (pinfunction "2_2") (pintype "passive"))
    )
    (net (code "123") (name "Net-(K1-I{slash}O-Pad1)") (class "Default")
      (node (ref "K1") (pin "1") (pinfunction "I/O_1") (pintype "passive"))
      (node (ref "P6") (pin "1") (pinfunction "1_1") (pintype "power_in"))
      (node (ref "P6") (pin "1A") (pinfunction "1A_1A") (pintype "power_in"))
      (node (ref "P6") (pin "1B") (pinfunction "1B_1B") (pintype "power_in"))
    )
    (net (code "124") (name "Net-(P6-Pad3)") (class "Default")
      (node (ref "P6") (pin "3") (pinfunction "3_3") (pintype "power_in"))
      (node (ref "P6") (pin "3A") (pinfunction "3A_3A") (pintype "power_in"))
      (node (ref "P6") (pin "3B") (pinfunction "3B_3B") (pintype "power_in"))
    )
    (net (code "125") (name "VCC") (class "Default")
      (node (ref "*") (pin "3") (pinfunction "VCC_3") (pintype "passive"))
      (node (ref "C9") (pin "2") (pinfunction "2_2") (pintype "passive"))
      (node (ref "ESP8266") (pin "1") (pinfunction "VCC_1") (pintype "passive"))
      (node (ref "ESP8266") (pin "6") (pinfunction "I0_0_6") (pintype "passive"))
      (node (ref "GPS") (pin "1") (pinfunction "1_1") (pintype "passive"))
      (node (ref "K1") (pin "2") (pinfunction "TAP1_2") (pintype "passive"))
      (node (ref "PM2.5/PM10") (pin "1") (pinfunction "1_1") (pintype "passive"))
      (node (ref "R11") (pin "1") (pinfunction "1_1") (pintype "passive"))
      (node (ref "VCC") (pin "1") (pinfunction "1_1") (pintype "passive"))
      (node (ref "VCC") (pin "2") (pinfunction "2_2") (pintype "passive"))
      (node (ref "VCC") (pin "3") (pinfunction "3_3") (pintype "passive"))
      (node (ref "VCC") (pin "4") (pinfunction "4_4") (pintype "passive"))
      (node (ref "VCC") (pin "5") (pinfunction "5_5") (pintype "passive"))
      (node (ref "VCC") (pin "6") (pinfunction "6_6") (pintype "passive"))
      (node (ref "串口屏") (pin "4") (pinfunction "VCC_4") (pintype "passive"))
      (node (ref "光照") (pin "1") (pinfunction "1_1") (pintype "passive"))
      (node (ref "烟雾") (pin "1") (pinfunction "1_1") (pintype "passive"))
      (node (ref "红外") (pin "1") (pinfunction "1_1") (pintype "passive"))
    )
    (net (code "126") (name "unconnected-(K1-I{slash}O-Pad3)") (class "Default")
      (node (ref "K1") (pin "3") (pinfunction "I/O_3") (pintype "passive"))
    )
    (net (code "127") (name "unconnected-(K1-I{slash}O2-Pad4)") (class "Default")
      (node (ref "K1") (pin "4") (pinfunction "I/O2_4") (pintype "passive"))
    )
    (net (code "128") (name "unconnected-(K1-I{slash}O2-Pad6)") (class "Default")
      (node (ref "K1") (pin "6") (pinfunction "I/O2_6") (pintype "passive"))
    )
    (net (code "129") (name "unconnected-(K1-TAP2-Pad5)") (class "Default")
      (node (ref "K1") (pin "5") (pinfunction "TAP2_5") (pintype "passive"))
    )
    (net (code "130") (name "unconnected-(ZET6-Pad6)") (class "Default")
      (node (ref "ZET6") (pin "6") (pinfunction "6_6") (pintype "passive+no_connect"))
    )
    (net (code "131") (name "unconnected-(ZET6-Pad106)") (class "Default")
      (node (ref "ZET6") (pin "106") (pinfunction "106_106") (pintype "passive+no_connect"))
    )
  )
)
